# digital-isolator-3in-1out-power.net
KiCad netlist of a schematic drawn in Altium Designer
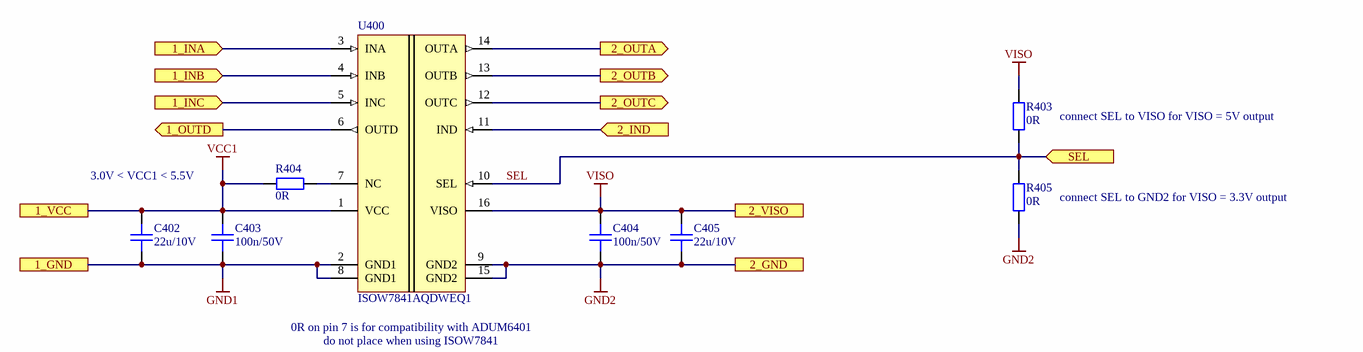
[diagram p0: digital-isolator-3in-1out-power.SchDoc]

(export (version "E")
  (design (tool "Eeschema 10.0.6"))
  (components
    (comp (ref "C402")
      (value "22u/10V")
      (footprint "CAPC3216X18N")
      (description "MLCC")
      (fields (field (name "PART NUMBER") "gen_C_ceramic_22u_10V_X7R_1206"))
      (libsource (lib "OE750") (part "C"))
    )
    (comp (ref "C403")
      (value "100n/50V")
      (footprint "CAPC1608X08N")
      (description "MLCC")
      (fields (field (name "PART NUMBER") "gen_C_ceramic_100n_50V_X7R_0603"))
      (libsource (lib "OE750") (part "C"))
    )
    (comp (ref "C404")
      (value "100n/50V")
      (footprint "CAPC1608X08N")
      (description "MLCC")
      (fields (field (name "PART NUMBER") "gen_C_ceramic_100n_50V_X7R_0603"))
      (libsource (lib "OE750") (part "C"))
    )
    (comp (ref "C405")
      (value "22u/10V")
      (footprint "CAPC3216X18N")
      (description "MLCC")
      (fields (field (name "PART NUMBER") "gen_C_ceramic_22u_10V_X7R_1206"))
      (libsource (lib "OE750") (part "C"))
    )
    (comp (ref "R403")
      (value "0R")
      (footprint "RESC1608X05N")
      (description "SMD Resistor 0R 0603")
      (fields (field (name "PART NUMBER") "gen_R_0R_0603") (field (name "POWER") "0.1W"))
      (libsource (lib "OE750") (part "R"))
    )
    (comp (ref "R404")
      (value "0R")
      (footprint "RESC1608X05N")
      (description "SMD Resistor 0R 0603")
      (fields (field (name "PART NUMBER") "gen_R_0R_0603") (field (name "POWER") "0.1W"))
      (libsource (lib "OE750") (part "R"))
    )
    (comp (ref "R405")
      (value "0R")
      (footprint "RESC1608X05N")
      (description "SMD Resistor 0R 0603")
      (fields (field (name "PART NUMBER") "gen_R_0R_0603") (field (name "POWER") "0.1W"))
      (libsource (lib "OE750") (part "R"))
    )
    (comp (ref "U400")
      (value "ISOW7841AQDWEQ1")
      (footprint "TI_DWE0016A")
      (fields (field (name "MANUFACTURER") "Texas Instruments"))
      (libsource (lib "OE750") (part "ISOW7841A"))
    )
  )
  (nets
    (net (code "1") (name "/1_INA") (class "Default")
      (node (ref "U400") (pin "3") (pinfunction "INA_3") (pintype "input"))
    )
    (net (code "2") (name "/1_INB") (class "Default")
      (node (ref "U400") (pin "4") (pinfunction "INB_4") (pintype "input"))
    )
    (net (code "3") (name "/1_INC") (class "Default")
      (node (ref "U400") (pin "5") (pinfunction "INC_5") (pintype "input"))
    )
    (net (code "4") (name "/1_OUTD") (class "Default")
      (node (ref "U400") (pin "6") (pinfunction "OUTD_6") (pintype "output"))
    )
    (net (code "5") (name "/2_IND") (class "Default")
      (node (ref "U400") (pin "11") (pinfunction "IND_11") (pintype "input"))
    )
    (net (code "6") (name "/2_OUTA") (class "Default")
      (node (ref "U400") (pin "14") (pinfunction "OUTA_14") (pintype "output"))
    )
    (net (code "7") (name "/2_OUTB") (class "Default")
      (node (ref "U400") (pin "13") (pinfunction "OUTB_13") (pintype "output"))
    )
    (net (code "8") (name "/2_OUTC") (class "Default")
      (node (ref "U400") (pin "12") (pinfunction "OUTC_12") (pintype "output"))
    )
    (net (code "9") (name "/SEL") (class "Default")
      (node (ref "R403") (pin "1") (pinfunction "1_1") (pintype "passive"))
      (node (ref "R405") (pin "2") (pinfunction "2_2") (pintype "passive"))
      (node (ref "U400") (pin "10") (pinfunction "SEL_10") (pintype "input"))
    )
    (net (code "10") (name "GND1") (class "Default")
      (node (ref "C402") (pin "1") (pinfunction "1_1") (pintype "passive"))
      (node (ref "C403") (pin "1") (pinfunction "1_1") (pintype "passive"))
      (node (ref "U400") (pin "2") (pinfunction "GND1_2") (pintype "power_in"))
      (node (ref "U400") (pin "8") (pinfunction "GND1_8") (pintype "power_in"))
    )
    (net (code "11") (name "GND2") (class "Default")
      (node (ref "C404") (pin "1") (pinfunction "1_1") (pintype "passive"))
      (node (ref "C405") (pin "1") (pinfunction "1_1") (pintype "passive"))
      (node (ref "R405") (pin "1") (pinfunction "1_1") (pintype "passive"))
      (node (ref "U400") (pin "15") (pinfunction "GND2_15") (pintype "power_in"))
      (node (ref "U400") (pin "9") (pinfunction "GND2_9") (pintype "power_in"))
    )
    (net (code "12") (name "Net-(U400-NC)") (class "Default")
      (node (ref "R404") (pin "1") (pinfunction "1_1") (pintype "passive"))
      (node (ref "U400") (pin "7") (pinfunction "NC_7") (pintype "passive"))
    )
    (net (code "13") (name "VCC1") (class "Default")
      (node (ref "C402") (pin "2") (pinfunction "2_2") (pintype "passive"))
      (node (ref "C403") (pin "2") (pinfunction "2_2") (pintype "passive"))
      (node (ref "R404") (pin "2") (pinfunction "2_2") (pintype "passive"))
      (node (ref "U400") (pin "1") (pinfunction "VCC_1") (pintype "power_in"))
    )
    (net (code "14") (name "VISO") (class "Default")
      (node (ref "C404") (pin "2") (pinfunction "2_2") (pintype "passive"))
      (node (ref "C405") (pin "2") (pinfunction "2_2") (pintype "passive"))
      (node (ref "R403") (pin "2") (pinfunction "2_2") (pintype "passive"))
      (node (ref "U400") (pin "16") (pinfunction "VISO_16") (pintype "power_in"))
    )
  )
)
